# BPW5020-Audio-Wing.net
KiCad netlist of a schematic drawn in EAGLE
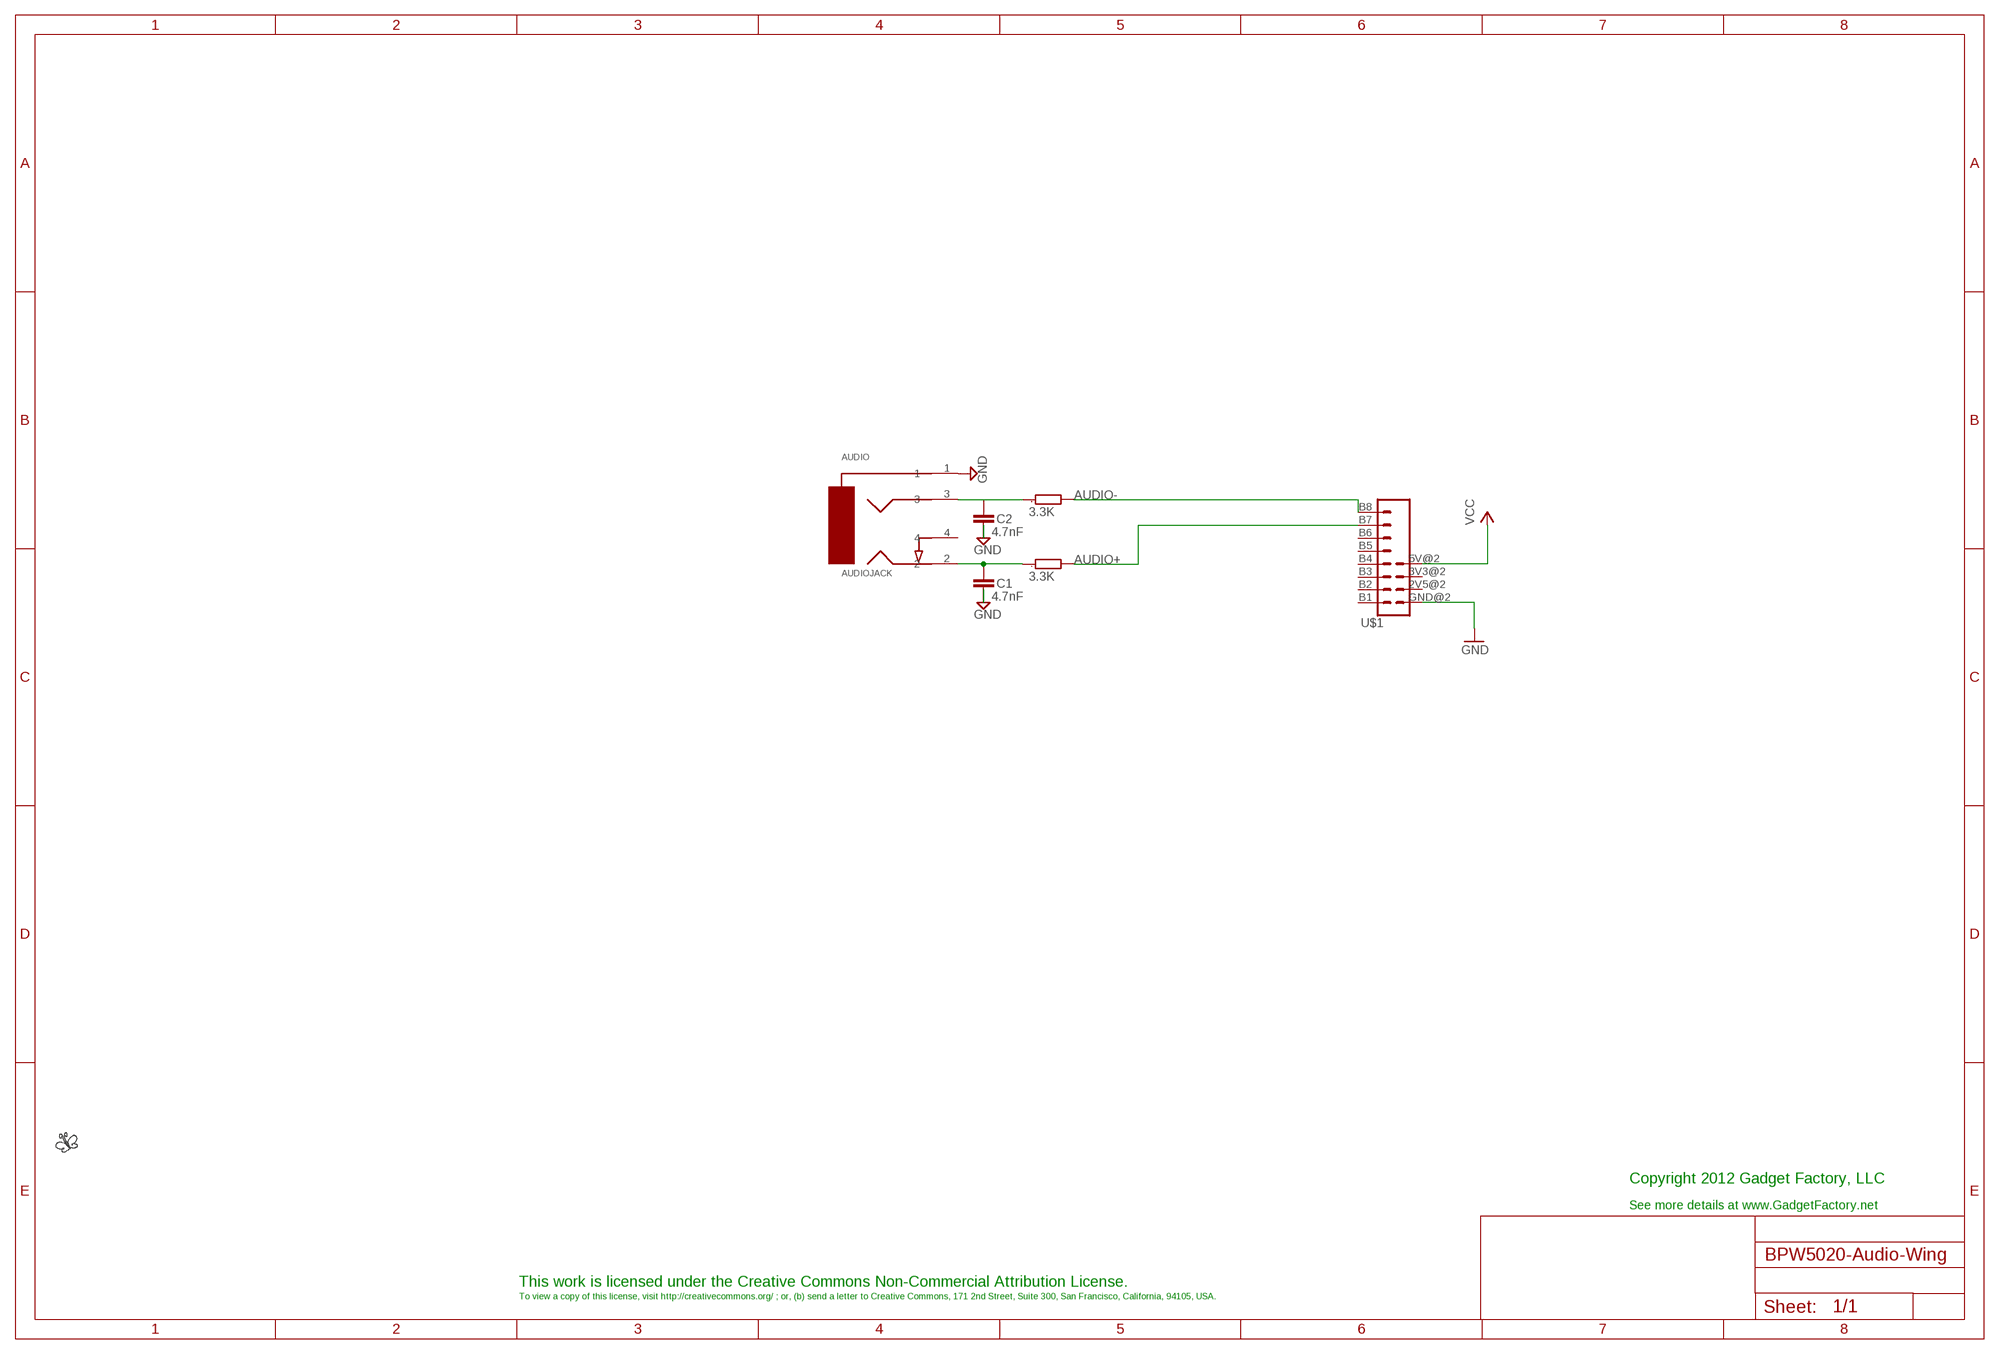
[diagram p0: schematic, sheet 1]

(export (version "E")
  (design (tool "Eeschema 10.0.6"))
  (components
    (comp (ref "AUDIO")
      (value "AUDIOJACK")
      (footprint "eagle-import:AUDJCK")
      (libsource (lib "eagle-import") (part "AUDIOJACK"))
    )
    (comp (ref "C1")
      (value "4.7nF")
      (footprint "eagle-import:C050-025X075")
      (libsource (lib "eagle-import") (part "C-EU050-025X075"))
    )
    (comp (ref "C2")
      (value "4.7nF")
      (footprint "eagle-import:C050-025X075")
      (libsource (lib "eagle-import") (part "C-EU050-025X075"))
    )
    (comp (ref "LOGO1")
      (value "BUTTERFLY_LOGO")
      (footprint "eagle-import:BUTTERFLY_LOGO")
      (libsource (lib "eagle-import") (part "BUTTERFLY_LOGO"))
    )
    (comp (ref "R1")
      (value "3.3K")
      (footprint "eagle-import:DUALRESISTOR")
      (libsource (lib "eagle-import") (part "R"))
    )
    (comp (ref "R2")
      (value "3.3K")
      (footprint "eagle-import:DUALRESISTOR")
      (libsource (lib "eagle-import") (part "R"))
    )
    (comp (ref "U$1")
      (value "WING_8BIT")
      (footprint "eagle-import:WINGSIDE_8BIT")
      (libsource (lib "eagle-import") (part "WING_8BIT"))
    )
  )
  (nets
    (net (code "1") (name "/AUDIO+") (class "Default")
      (node (ref "R1") (pin "2") (pinfunction "2_2") (pintype "passive"))
      (node (ref "U$1") (pin "B7") (pinfunction "7_B7") (pintype "passive"))
    )
    (net (code "2") (name "/AUDIO-") (class "Default")
      (node (ref "R2") (pin "2") (pinfunction "2_2") (pintype "passive"))
      (node (ref "U$1") (pin "B8") (pinfunction "8_B8") (pintype "passive"))
    )
    (net (code "3") (name "GND") (class "Default")
      (node (ref "AUDIO") (pin "1") (pinfunction "1_1") (pintype "bidirectional"))
      (node (ref "C1") (pin "2") (pinfunction "2_2") (pintype "passive"))
      (node (ref "C2") (pin "2") (pinfunction "2_2") (pintype "passive"))
      (node (ref "U$1") (pin "GND@2") (pinfunction "GND_GND@2") (pintype "passive"))
    )
    (net (code "4") (name "Net-(AUDIO-Pad2)") (class "Default")
      (node (ref "AUDIO") (pin "2") (pinfunction "2_2") (pintype "bidirectional"))
      (node (ref "C1") (pin "1") (pinfunction "1_1") (pintype "passive"))
      (node (ref "R1") (pin "1") (pinfunction "1_1") (pintype "passive"))
    )
    (net (code "5") (name "Net-(AUDIO-Pad3)") (class "Default")
      (node (ref "AUDIO") (pin "3") (pinfunction "3_3") (pintype "bidirectional"))
      (node (ref "C2") (pin "1") (pinfunction "1_1") (pintype "passive"))
      (node (ref "R2") (pin "1") (pinfunction "1_1") (pintype "passive"))
    )
    (net (code "6") (name "VCC") (class "Default")
      (node (ref "U$1") (pin "5V@2") (pinfunction "5V_5V@2") (pintype "passive"))
    )
    (net (code "7") (name "unconnected-(AUDIO-Pad4)") (class "Default")
      (node (ref "AUDIO") (pin "4") (pinfunction "4_4") (pintype "bidirectional"))
    )
    (net (code "8") (name "unconnected-(U$1-1-PadB1)") (class "Default")
      (node (ref "U$1") (pin "B1") (pinfunction "1_B1") (pintype "passive"))
    )
    (net (code "9") (name "unconnected-(U$1-2-PadB2)") (class "Default")
      (node (ref "U$1") (pin "B2") (pinfunction "2_B2") (pintype "passive"))
    )
    (net (code "10") (name "unconnected-(U$1-2V5-Pad2V5@2)") (class "Default")
      (node (ref "U$1") (pin "2V5@2") (pinfunction "2V5_2V5@2") (pintype "passive"))
    )
    (net (code "11") (name "unconnected-(U$1-3-PadB3)") (class "Default")
      (node (ref "U$1") (pin "B3") (pinfunction "3_B3") (pintype "passive"))
    )
    (net (code "12") (name "unconnected-(U$1-3V3-Pad3V3@2)") (class "Default")
      (node (ref "U$1") (pin "3V3@2") (pinfunction "3V3_3V3@2") (pintype "passive"))
    )
    (net (code "13") (name "unconnected-(U$1-4-PadB4)") (class "Default")
      (node (ref "U$1") (pin "B4") (pinfunction "4_B4") (pintype "passive"))
    )
    (net (code "14") (name "unconnected-(U$1-5-PadB5)") (class "Default")
      (node (ref "U$1") (pin "B5") (pinfunction "5_B5") (pintype "passive"))
    )
    (net (code "15") (name "unconnected-(U$1-6-PadB6)") (class "Default")
      (node (ref "U$1") (pin "B6") (pinfunction "6_B6") (pintype "passive"))
    )
  )
)
